# tick-box-1591A-mk-2_2.net
KiCad netlist of a schematic drawn in EAGLE
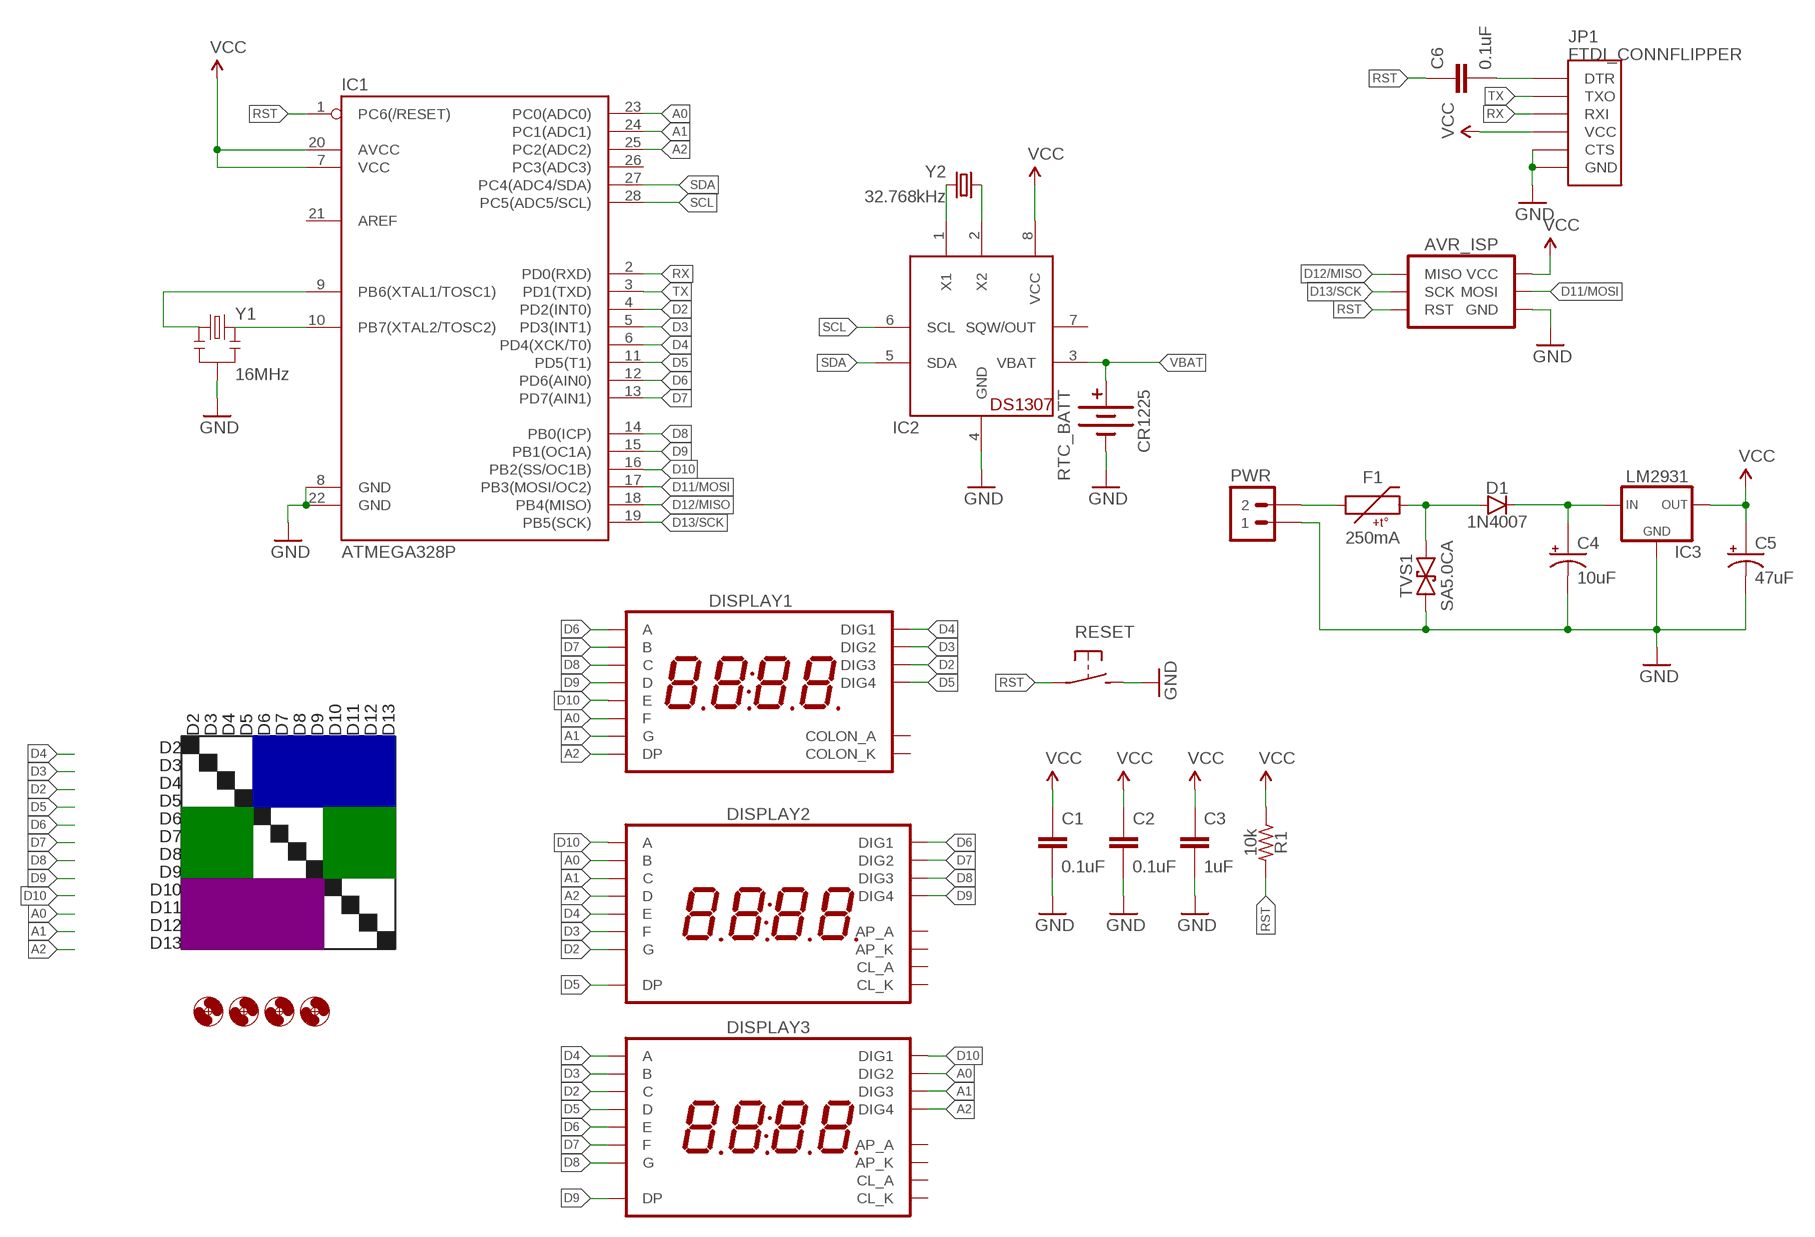
[diagram p0: schematic, sheet 1]

(export (version "E")
  (design (tool "Eeschema 10.0.6"))
  (components
    (comp (ref "AVR_ISP")
      (value "AVR_SPI_PRG_6PTH")
      (footprint "eagle-import:2X3")
      (libsource (lib "eagle-import") (part "AVR_SPI_PRG_6PTH"))
    )
    (comp (ref "C1")
      (value "0.1uF")
      (footprint "eagle-import:C025-024X044")
      (libsource (lib "eagle-import") (part "CAPACITOR-CERAMIC025-024X044"))
    )
    (comp (ref "C2")
      (value "0.1uF")
      (footprint "eagle-import:C025-024X044")
      (libsource (lib "eagle-import") (part "CAPACITOR-CERAMIC025-024X044"))
    )
    (comp (ref "C3")
      (value "1uF")
      (footprint "eagle-import:C025-024X044")
      (libsource (lib "eagle-import") (part "CAPACITOR-CERAMIC025-024X044"))
    )
    (comp (ref "C4")
      (value "10uF")
      (footprint "eagle-import:E2-5")
      (libsource (lib "eagle-import") (part "CAPACITOR-POLARIZEDE2-5"))
    )
    (comp (ref "C5")
      (value "47uF")
      (footprint "eagle-import:E2,5-6")
      (libsource (lib "eagle-import") (part "CAPACITOR-POLARIZEDE2.5-6"))
    )
    (comp (ref "C6")
      (value "0.1uF")
      (footprint "eagle-import:C025-024X044")
      (libsource (lib "eagle-import") (part "CAPACITOR-CERAMIC025-024X044"))
    )
    (comp (ref "D1")
      (value "1N4007")
      (footprint "eagle-import:DIODE-10.16MM")
      (libsource (lib "eagle-import") (part "DIODEPTH-10.68MM"))
    )
    (comp (ref "DISPLAY1")
      (value "7SEG_4DIGIT_COLON14.2MM-CC-NS")
      (footprint "eagle-import:7SEG_4DIG_NS")
      (libsource (lib "eagle-import") (part "7SEG_4DIGIT_COLON14.2MM-CC-NS"))
    )
    (comp (ref "DISPLAY2")
      (value "7SEG_4DIGIT_COLON_APOS")
      (footprint "eagle-import:7SEG_4DIG_10MM")
      (libsource (lib "eagle-import") (part "7SEG_4DIGIT_COLON_APOS"))
    )
    (comp (ref "DISPLAY3")
      (value "7SEG_4DIGIT_COLON_APOS")
      (footprint "eagle-import:7SEG_4DIG_10MM")
      (libsource (lib "eagle-import") (part "7SEG_4DIGIT_COLON_APOS"))
    )
    (comp (ref "F1")
      (value "250mA")
      (footprint "eagle-import:PTC-PTH-5.08MM")
      (libsource (lib "eagle-import") (part "PTCPTH-5.08MM"))
    )
    (comp (ref "H1")
      (value "HOLE#2")
      (footprint "eagle-import:HOLE-#2")
      (libsource (lib "eagle-import") (part "HOLE#2"))
    )
    (comp (ref "H2")
      (value "HOLE#2")
      (footprint "eagle-import:HOLE-#2")
      (libsource (lib "eagle-import") (part "HOLE#2"))
    )
    (comp (ref "H3")
      (value "HOLE#2")
      (footprint "eagle-import:HOLE-#2")
      (libsource (lib "eagle-import") (part "HOLE#2"))
    )
    (comp (ref "H4")
      (value "HOLE#2")
      (footprint "eagle-import:HOLE-#2")
      (libsource (lib "eagle-import") (part "HOLE#2"))
    )
    (comp (ref "IC1")
      (value "ATMEGA328P")
      (footprint "eagle-import:DIL28-3")
      (libsource (lib "eagle-import") (part "ATMEGA328P_PDIP"))
    )
    (comp (ref "IC2")
      (value "DS1307")
      (footprint "eagle-import:DIL08")
      (libsource (lib "eagle-import") (part "DS1307"))
    )
    (comp (ref "IC3")
      (value "LM2931")
      (footprint "eagle-import:TO-92-AMMO")
      (libsource (lib "eagle-import") (part "V_REG_78XXTO-92-INLINE"))
    )
    (comp (ref "JP1")
      (value "FTDI_CONNFLIPPER")
      (footprint "eagle-import:FTDI_CONN_FLIP")
      (libsource (lib "eagle-import") (part "FTDI_CONNFLIPPER"))
    )
    (comp (ref "PWR")
      (value "M02PTH-CENTERED")
      (footprint "eagle-import:1X02-CENTER")
      (libsource (lib "eagle-import") (part "M02PTH-CENTERED"))
    )
    (comp (ref "R1")
      (value "10k")
      (footprint "eagle-import:RESISTOR-AXIAL-PTH-6.35MM")
      (libsource (lib "eagle-import") (part "RESISTORPTH-AXIAL-6.35MM"))
    )
    (comp (ref "RESET")
      (value "SPST-NO-TACT3MM-PTH-SMALL-PADS")
      (footprint "eagle-import:DTS-3-SMALL-PADS")
      (libsource (lib "eagle-import") (part "SPST-NO-TACT3MM-PTH-SMALL-PADS"))
    )
    (comp (ref "RTC_BATT")
      (value "CR1225")
      (footprint "eagle-import:BATTCON_12MM_PTH_TOPLOAD")
      (libsource (lib "eagle-import") (part "BATTERY12PTH_TOPLOAD"))
    )
    (comp (ref "TVS1")
      (value "SA5.0CA")
      (footprint "eagle-import:DO-41-TVS-BI-10.16MM")
      (libsource (lib "eagle-import") (part "TVSDO-41-10.16MM"))
    )
    (comp (ref "Y1")
      (value "16MHz")
      (footprint "eagle-import:RESONATOR-PTH")
      (libsource (lib "eagle-import") (part "RESONATORPTH"))
    )
    (comp (ref "Y2")
      (value "32.768kHz")
      (footprint "eagle-import:TC26H")
      (libsource (lib "eagle-import") (part "CRYSTALTC26H"))
    )
  )
  (nets
    (net (code "1") (name "A0") (class "Default")
      (node (ref "DISPLAY1") (pin "P$12") (pinfunction "F_P$12") (pintype "passive"))
      (node (ref "DISPLAY2") (pin "16") (pinfunction "B_16") (pintype "passive"))
      (node (ref "DISPLAY3") (pin "2") (pinfunction "DIG2_2") (pintype "passive"))
      (node (ref "IC1") (pin "23") (pinfunction "PC0(ADC0)_23") (pintype "bidirectional"))
    )
    (net (code "2") (name "A1") (class "Default")
      (node (ref "DISPLAY1") (pin "P$5") (pinfunction "G_P$5") (pintype "passive"))
      (node (ref "DISPLAY2") (pin "13") (pinfunction "C_13") (pintype "passive"))
      (node (ref "DISPLAY3") (pin "6") (pinfunction "DIG3_6") (pintype "passive"))
      (node (ref "IC1") (pin "24") (pinfunction "PC1(ADC1)_24") (pintype "bidirectional"))
    )
    (net (code "3") (name "A2") (class "Default")
      (node (ref "DISPLAY1") (pin "P$3") (pinfunction "DP_P$3") (pintype "passive"))
      (node (ref "DISPLAY2") (pin "3") (pinfunction "D_3") (pintype "passive"))
      (node (ref "DISPLAY3") (pin "8") (pinfunction "DIG4_8") (pintype "passive"))
      (node (ref "IC1") (pin "25") (pinfunction "PC2(ADC2)_25") (pintype "bidirectional"))
    )
    (net (code "4") (name "D2") (class "Default")
      (node (ref "DISPLAY1") (pin "P$10") (pinfunction "DIG3_P$10") (pintype "passive"))
      (node (ref "DISPLAY2") (pin "15") (pinfunction "G_15") (pintype "passive"))
      (node (ref "DISPLAY3") (pin "13") (pinfunction "C_13") (pintype "passive"))
      (node (ref "IC1") (pin "4") (pinfunction "PD2(INT0)_4") (pintype "bidirectional"))
    )
    (net (code "5") (name "D3") (class "Default")
      (node (ref "DISPLAY1") (pin "P$11") (pinfunction "DIG2_P$11") (pintype "passive"))
      (node (ref "DISPLAY2") (pin "11") (pinfunction "F_11") (pintype "passive"))
      (node (ref "DISPLAY3") (pin "16") (pinfunction "B_16") (pintype "passive"))
      (node (ref "IC1") (pin "5") (pinfunction "PD3(INT1)_5") (pintype "bidirectional"))
    )
    (net (code "6") (name "D4") (class "Default")
      (node (ref "DISPLAY1") (pin "P$14") (pinfunction "DIG1_P$14") (pintype "passive"))
      (node (ref "DISPLAY2") (pin "5") (pinfunction "E_5") (pintype "passive"))
      (node (ref "DISPLAY3") (pin "14") (pinfunction "A_14") (pintype "passive"))
      (node (ref "IC1") (pin "6") (pinfunction "PD4(XCK/T0)_6") (pintype "bidirectional"))
    )
    (net (code "7") (name "D5") (class "Default")
      (node (ref "DISPLAY1") (pin "P$6") (pinfunction "DIG4_P$6") (pintype "passive"))
      (node (ref "DISPLAY2") (pin "7") (pinfunction "DP_7") (pintype "passive"))
      (node (ref "DISPLAY3") (pin "3") (pinfunction "D_3") (pintype "passive"))
      (node (ref "IC1") (pin "11") (pinfunction "PD5(T1)_11") (pintype "bidirectional"))
    )
    (net (code "8") (name "D6") (class "Default")
      (node (ref "DISPLAY1") (pin "P$13") (pinfunction "A_P$13") (pintype "passive"))
      (node (ref "DISPLAY2") (pin "1") (pinfunction "DIG1_1") (pintype "passive"))
      (node (ref "DISPLAY3") (pin "5") (pinfunction "E_5") (pintype "passive"))
      (node (ref "IC1") (pin "12") (pinfunction "PD6(AIN0)_12") (pintype "bidirectional"))
    )
    (net (code "9") (name "D7") (class "Default")
      (node (ref "DISPLAY1") (pin "P$9") (pinfunction "B_P$9") (pintype "passive"))
      (node (ref "DISPLAY2") (pin "2") (pinfunction "DIG2_2") (pintype "passive"))
      (node (ref "DISPLAY3") (pin "11") (pinfunction "F_11") (pintype "passive"))
      (node (ref "IC1") (pin "13") (pinfunction "PD7(AIN1)_13") (pintype "bidirectional"))
    )
    (net (code "10") (name "D8") (class "Default")
      (node (ref "DISPLAY1") (pin "P$4") (pinfunction "C_P$4") (pintype "passive"))
      (node (ref "DISPLAY2") (pin "6") (pinfunction "DIG3_6") (pintype "passive"))
      (node (ref "DISPLAY3") (pin "15") (pinfunction "G_15") (pintype "passive"))
      (node (ref "IC1") (pin "14") (pinfunction "PB0(ICP)_14") (pintype "bidirectional"))
    )
    (net (code "11") (name "D9") (class "Default")
      (node (ref "DISPLAY1") (pin "P$2") (pinfunction "D_P$2") (pintype "passive"))
      (node (ref "DISPLAY2") (pin "8") (pinfunction "DIG4_8") (pintype "passive"))
      (node (ref "DISPLAY3") (pin "7") (pinfunction "DP_7") (pintype "passive"))
      (node (ref "IC1") (pin "15") (pinfunction "PB1(OC1A)_15") (pintype "bidirectional"))
    )
    (net (code "12") (name "D10") (class "Default")
      (node (ref "DISPLAY1") (pin "P$1") (pinfunction "E_P$1") (pintype "passive"))
      (node (ref "DISPLAY2") (pin "14") (pinfunction "A_14") (pintype "passive"))
      (node (ref "DISPLAY3") (pin "1") (pinfunction "DIG1_1") (pintype "passive"))
      (node (ref "IC1") (pin "16") (pinfunction "PB2(SS/OC1B)_16") (pintype "bidirectional"))
    )
    (net (code "13") (name "D11{slash}MOSI") (class "Default")
      (node (ref "AVR_ISP") (pin "4") (pinfunction "MOSI_4") (pintype "passive"))
      (node (ref "IC1") (pin "17") (pinfunction "PB3(MOSI/OC2)_17") (pintype "bidirectional"))
    )
    (net (code "14") (name "D12{slash}MISO") (class "Default")
      (node (ref "AVR_ISP") (pin "1") (pinfunction "MISO_1") (pintype "passive"))
      (node (ref "IC1") (pin "18") (pinfunction "PB4(MISO)_18") (pintype "bidirectional"))
    )
    (net (code "15") (name "D13{slash}SCK") (class "Default")
      (node (ref "AVR_ISP") (pin "3") (pinfunction "SCK_3") (pintype "passive"))
      (node (ref "IC1") (pin "19") (pinfunction "PB5(SCK)_19") (pintype "bidirectional"))
    )
    (net (code "16") (name "GND") (class "Default")
      (node (ref "AVR_ISP") (pin "6") (pinfunction "GND_6") (pintype "passive"))
      (node (ref "C1") (pin "2") (pinfunction "2_2") (pintype "passive"))
      (node (ref "C2") (pin "2") (pinfunction "2_2") (pintype "passive"))
      (node (ref "C3") (pin "2") (pinfunction "2_2") (pintype "passive"))
      (node (ref "C4") (pin "-") (pinfunction "-_-") (pintype "passive"))
      (node (ref "C5") (pin "-") (pinfunction "-_-") (pintype "passive"))
      (node (ref "IC1") (pin "22") (pinfunction "GND_22") (pintype "bidirectional"))
      (node (ref "IC1") (pin "8") (pinfunction "GND_8") (pintype "bidirectional"))
      (node (ref "IC2") (pin "4") (pinfunction "GND_4") (pintype "power_in"))
      (node (ref "IC3") (pin "2") (pinfunction "GND_2") (pintype "bidirectional"))
      (node (ref "JP1") (pin "CTS") (pinfunction "CTS_CTS") (pintype "bidirectional"))
      (node (ref "JP1") (pin "GND") (pinfunction "GND_GND") (pintype "bidirectional"))
      (node (ref "PWR") (pin "1") (pinfunction "1_1") (pintype "passive"))
      (node (ref "RESET") (pin "2") (pinfunction "2_2") (pintype "passive"))
      (node (ref "RTC_BATT") (pin "-") (pinfunction "-_-") (pintype "power_in"))
      (node (ref "TVS1") (pin "P$1") (pinfunction "1_P$1") (pintype "passive"))
      (node (ref "Y1") (pin "2") (pinfunction "2_2") (pintype "passive"))
    )
    (net (code "17") (name "Net-(C6-Pad2)") (class "Default")
      (node (ref "C6") (pin "2") (pinfunction "2_2") (pintype "passive"))
      (node (ref "JP1") (pin "DTR") (pinfunction "DTR_DTR") (pintype "bidirectional"))
    )
    (net (code "18") (name "Net-(F1-1)") (class "Default")
      (node (ref "F1") (pin "P$1") (pinfunction "1_P$1") (pintype "passive"))
      (node (ref "PWR") (pin "2") (pinfunction "2_2") (pintype "passive"))
    )
    (net (code "19") (name "Net-(F1-2)") (class "Default")
      (node (ref "D1") (pin "A") (pinfunction "A_A") (pintype "passive"))
      (node (ref "F1") (pin "P$2") (pinfunction "2_P$2") (pintype "passive"))
      (node (ref "TVS1") (pin "P$2") (pinfunction "2_P$2") (pintype "passive"))
    )
    (net (code "20") (name "Net-(IC1-PB6(XTAL1{slash}TOSC1))") (class "Default")
      (node (ref "IC1") (pin "9") (pinfunction "PB6(XTAL1/TOSC1)_9") (pintype "bidirectional"))
      (node (ref "Y1") (pin "1") (pinfunction "1_1") (pintype "passive"))
    )
    (net (code "21") (name "Net-(IC1-PB7(XTAL2{slash}TOSC2))") (class "Default")
      (node (ref "IC1") (pin "10") (pinfunction "PB7(XTAL2/TOSC2)_10") (pintype "bidirectional"))
      (node (ref "Y1") (pin "3") (pinfunction "3_3") (pintype "passive"))
    )
    (net (code "22") (name "Net-(IC2-X1)") (class "Default")
      (node (ref "IC2") (pin "1") (pinfunction "X1_1") (pintype "passive"))
      (node (ref "Y2") (pin "2") (pinfunction "2_2") (pintype "passive"))
    )
    (net (code "23") (name "Net-(IC2-X2)") (class "Default")
      (node (ref "IC2") (pin "2") (pinfunction "X2_2") (pintype "passive"))
      (node (ref "Y2") (pin "1") (pinfunction "1_1") (pintype "passive"))
    )
    (net (code "24") (name "Net-(IC3-IN)") (class "Default")
      (node (ref "C4") (pin "+") (pinfunction "+_+") (pintype "passive"))
      (node (ref "D1") (pin "C") (pinfunction "C_C") (pintype "passive"))
      (node (ref "IC3") (pin "1") (pinfunction "IN_1") (pintype "bidirectional"))
    )
    (net (code "25") (name "RST") (class "Default")
      (node (ref "AVR_ISP") (pin "5") (pinfunction "RST_5") (pintype "passive"))
      (node (ref "C6") (pin "1") (pinfunction "1_1") (pintype "passive"))
      (node (ref "IC1") (pin "1") (pinfunction "PC6(/RESET)_1") (pintype "bidirectional"))
      (node (ref "R1") (pin "P$2") (pinfunction "2_P$2") (pintype "passive"))
      (node (ref "RESET") (pin "1") (pinfunction "1_1") (pintype "passive"))
    )
    (net (code "26") (name "RX") (class "Default")
      (node (ref "IC1") (pin "2") (pinfunction "PD0(RXD)_2") (pintype "bidirectional"))
      (node (ref "JP1") (pin "RXI") (pinfunction "RXI_RXI") (pintype "bidirectional"))
    )
    (net (code "27") (name "SCL") (class "Default")
      (node (ref "IC1") (pin "28") (pinfunction "PC5(ADC5/SCL)_28") (pintype "bidirectional"))
      (node (ref "IC2") (pin "6") (pinfunction "SCL_6") (pintype "bidirectional"))
    )
    (net (code "28") (name "SDA") (class "Default")
      (node (ref "IC1") (pin "27") (pinfunction "PC4(ADC4/SDA)_27") (pintype "bidirectional"))
      (node (ref "IC2") (pin "5") (pinfunction "SDA_5") (pintype "bidirectional"))
    )
    (net (code "29") (name "TX") (class "Default")
      (node (ref "IC1") (pin "3") (pinfunction "PD1(TXD)_3") (pintype "bidirectional"))
      (node (ref "JP1") (pin "TXO") (pinfunction "TXO_TXO") (pintype "bidirectional"))
    )
    (net (code "30") (name "VBAT") (class "Default")
      (node (ref "IC2") (pin "3") (pinfunction "VBAT_3") (pintype "power_in"))
      (node (ref "RTC_BATT") (pin "+") (pinfunction "+_+") (pintype "power_in"))
    )
    (net (code "31") (name "VCC") (class "Default")
      (node (ref "AVR_ISP") (pin "2") (pinfunction "VCC_2") (pintype "passive"))
      (node (ref "C1") (pin "1") (pinfunction "1_1") (pintype "passive"))
      (node (ref "C2") (pin "1") (pinfunction "1_1") (pintype "passive"))
      (node (ref "C3") (pin "1") (pinfunction "1_1") (pintype "passive"))
      (node (ref "C5") (pin "+") (pinfunction "+_+") (pintype "passive"))
      (node (ref "IC1") (pin "20") (pinfunction "AVCC_20") (pintype "bidirectional"))
      (node (ref "IC1") (pin "7") (pinfunction "VCC_7") (pintype "bidirectional"))
      (node (ref "IC2") (pin "8") (pinfunction "VCC_8") (pintype "power_in"))
      (node (ref "IC3") (pin "3") (pinfunction "OUT_3") (pintype "bidirectional"))
      (node (ref "JP1") (pin "VCC") (pinfunction "VCC_VCC") (pintype "bidirectional"))
      (node (ref "R1") (pin "P$1") (pinfunction "1_P$1") (pintype "passive"))
    )
    (net (code "32") (name "unconnected-(DISPLAY1-COLON_A-PadP$8)") (class "Default")
      (node (ref "DISPLAY1") (pin "P$8") (pinfunction "COLON_A_P$8") (pintype "passive"))
    )
    (net (code "33") (name "unconnected-(DISPLAY1-COLON_K-PadP$7)") (class "Default")
      (node (ref "DISPLAY1") (pin "P$7") (pinfunction "COLON_K_P$7") (pintype "passive"))
    )
    (net (code "34") (name "unconnected-(DISPLAY2-AP_A-Pad10)") (class "Default")
      (node (ref "DISPLAY2") (pin "10") (pinfunction "AP_A_10") (pintype "bidirectional"))
    )
    (net (code "35") (name "unconnected-(DISPLAY2-AP_K-Pad9)") (class "Default")
      (node (ref "DISPLAY2") (pin "9") (pinfunction "AP_K_9") (pintype "bidirectional"))
    )
    (net (code "36") (name "unconnected-(DISPLAY2-CL_A-Pad4)") (class "Default")
      (node (ref "DISPLAY2") (pin "4") (pinfunction "CL_A_4") (pintype "passive"))
    )
    (net (code "37") (name "unconnected-(DISPLAY2-CL_K-Pad12)") (class "Default")
      (node (ref "DISPLAY2") (pin "12") (pinfunction "CL_K_12") (pintype "passive"))
    )
    (net (code "38") (name "unconnected-(DISPLAY3-AP_A-Pad10)") (class "Default")
      (node (ref "DISPLAY3") (pin "10") (pinfunction "AP_A_10") (pintype "bidirectional"))
    )
    (net (code "39") (name "unconnected-(DISPLAY3-AP_K-Pad9)") (class "Default")
      (node (ref "DISPLAY3") (pin "9") (pinfunction "AP_K_9") (pintype "bidirectional"))
    )
    (net (code "40") (name "unconnected-(DISPLAY3-CL_A-Pad4)") (class "Default")
      (node (ref "DISPLAY3") (pin "4") (pinfunction "CL_A_4") (pintype "passive"))
    )
    (net (code "41") (name "unconnected-(DISPLAY3-CL_K-Pad12)") (class "Default")
      (node (ref "DISPLAY3") (pin "12") (pinfunction "CL_K_12") (pintype "passive"))
    )
    (net (code "42") (name "unconnected-(IC1-AREF-Pad21)") (class "Default")
      (node (ref "IC1") (pin "21") (pinfunction "AREF_21") (pintype "bidirectional"))
    )
    (net (code "43") (name "unconnected-(IC1-PC3(ADC3)-Pad26)") (class "Default")
      (node (ref "IC1") (pin "26") (pinfunction "PC3(ADC3)_26") (pintype "bidirectional"))
    )
    (net (code "44") (name "unconnected-(IC2-SQW{slash}OUT-Pad7)") (class "Default")
      (node (ref "IC2") (pin "7") (pinfunction "SQW/OUT_7") (pintype "bidirectional"))
    )
  )
)
